# BufferBiasAmp.net
KiCad netlist of a schematic drawn in Altium Designer
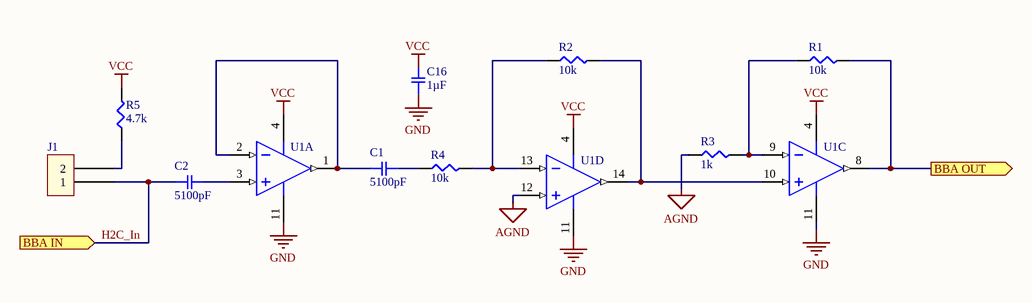
[diagram p0: BufferBiasAmp.SchDoc]

(export (version "E")
  (design (tool "Eeschema 10.0.6"))
  (components
    (comp (ref "C1")
      (value "5100pF")
      (footprint "SMD-0603C")
      (description "CAP CER 5100PF 50V U2J 0603")
      (fields
        (field (name "MANUFACTURER") "Murata Electronics North America")
        (field (name "MANUFACTURER PART NUMBER") "GRM1887U1H512JA01D")
      )
      (libsource (lib "capacitor_murata_0603") (part "GRM1887U1H512JA01D"))
    )
    (comp (ref "C2")
      (value "5100pF")
      (footprint "SMD-0603C")
      (description "CAP CER 5100PF 50V U2J 0603")
      (fields
        (field (name "DIGI-KEY PART NUMBER") "490-6399-1-ND")
        (field (name "PART NUMBER") "GRM1887U1H512JA01D")
      )
      (libsource (lib "capacitor_murata_0603") (part "GRM1887U1H512JA01D"))
    )
    (comp (ref "C16")
      (value "1µF")
      (footprint "SMD-0603C")
      (description "CAP CER 1UF 16V X7R 0603")
      (fields
        (field (name "MANUFACTURER") "Samsung Electro-Mechanics")
        (field (name "MANUFACTURER PART NUMBER") "CL10A105KA8NNNC")
      )
      (libsource (lib "capacitor_murata_0603") (part "GCM188R71C105KA64D"))
    )
    (comp (ref "J1")
      (value "Header")
      (footprint "1x2 Header")
      (description "CONN HEADER VERT 2POS 2.54MM")
      (libsource (lib "URC_Lib") (part "1x2 Header"))
    )
    (comp (ref "R1")
      (value "10k")
      (footprint "SMD-0603-RES")
      (description "RES SMD 10K OHM 1% 1/10W 0603")
      (fields
        (field (name "MANUFACTURER") "Panasonic Electronic Components")
        (field (name "MANUFACTURER PART NUMBER") "RNCP0603FTD10K0")
      )
      (libsource (lib "Panasonic_resistor_0603") (part "ERJ-3EKF1002V"))
    )
    (comp (ref "R2")
      (value "10k")
      (footprint "SMD-0603-RES")
      (description "RES SMD 10K OHM 1% 1/10W 0603")
      (fields
        (field (name "MANUFACTURER") "Panasonic Electronic Components")
        (field (name "MANUFACTURER PART NUMBER") "RNCP0603FTD10K0")
      )
      (libsource (lib "Panasonic_resistor_0603") (part "ERJ-3EKF1002V"))
    )
    (comp (ref "R3")
      (value "1k")
      (footprint "SMD-0603-RES")
      (description "RES SMD 1K OHM 1% 1/10W 0603")
      (fields
        (field (name "MANUFACTURER") "Stackpole Electronics Inc")
        (field (name "MANUFACTURER PART NUMBER") "RNCP0603FTD1K00")
      )
      (libsource (lib "Panasonic_resistor_0603") (part "ERJ-3EKF1001V"))
    )
    (comp (ref "R4")
      (value "10k")
      (footprint "SMD-0603-RES")
      (description "RES SMD 10K OHM 1% 1/10W 0603")
      (fields
        (field (name "MANUFACTURER") "Panasonic Electronic Components")
        (field (name "MANUFACTURER PART NUMBER") "RNCP0603FTD10K0")
      )
      (libsource (lib "Panasonic_resistor_0603") (part "ERJ-3EKF1002V"))
    )
    (comp (ref "R5")
      (value "4.7k")
      (footprint "SMD-0603-RES")
      (description "RES SMD 4.7K OHM 1% 1/10W 0603")
      (fields
        (field (name "MANUFACTURER") "Panasonic Electronic Components")
        (field (name "MANUFACTURER PART NUMBER") "ERJ-3EKF4701V")
      )
      (libsource (lib "Panasonic_resistor_0603") (part "ERJ-3EKF4701V"))
    )
    (comp (ref "U1")
      (value "OPA1604AIPWR")
      (footprint "PW0014A_N")
      (fields (field (name "MANUFACTURER") "Texas Instruments"))
      (libsource (lib "Altium Content Vault") (part "TI-OPA16X4_4XXX-14"))
    )
  )
  (nets
    (net (code "1") (name "/BBA OUT") (class "Default")
      (node (ref "R1") (pin "2") (pinfunction "2_2") (pintype "passive"))
      (node (ref "U1") (pin "8") (pinfunction "OUT_C_8") (pintype "output"))
    )
    (net (code "2") (name "/H2C_In") (class "Default")
      (node (ref "C2") (pin "1") (pinfunction "1_1") (pintype "passive"))
      (node (ref "J1") (pin "1") (pinfunction "1_1") (pintype "passive"))
    )
    (net (code "3") (name "AGND") (class "Default")
      (node (ref "R3") (pin "1") (pinfunction "1_1") (pintype "passive"))
      (node (ref "U1") (pin "12") (pinfunction "IN_D+_12") (pintype "input"))
    )
    (net (code "4") (name "GND") (class "Default")
      (node (ref "C16") (pin "1") (pinfunction "1_1") (pintype "passive"))
      (node (ref "U1") (pin "11") (pinfunction "V-_11") (pintype "power_in"))
    )
    (net (code "5") (name "Net-(C1-Pad1)") (class "Default")
      (node (ref "C1") (pin "1") (pinfunction "1_1") (pintype "passive"))
      (node (ref "R4") (pin "1") (pinfunction "1_1") (pintype "passive"))
    )
    (net (code "6") (name "Net-(J1-Pad2)") (class "Default")
      (node (ref "J1") (pin "2") (pinfunction "2_2") (pintype "passive"))
      (node (ref "R5") (pin "1") (pinfunction "1_1") (pintype "passive"))
    )
    (net (code "7") (name "Net-(U1A-IN_A+)") (class "Default")
      (node (ref "C2") (pin "2") (pinfunction "2_2") (pintype "passive"))
      (node (ref "U1") (pin "3") (pinfunction "IN_A+_3") (pintype "input"))
    )
    (net (code "8") (name "Net-(U1A-IN_A-)") (class "Default")
      (node (ref "C1") (pin "2") (pinfunction "2_2") (pintype "passive"))
      (node (ref "U1") (pin "1") (pinfunction "OUT_A_1") (pintype "output"))
      (node (ref "U1") (pin "2") (pinfunction "IN_A-_2") (pintype "input"))
    )
    (net (code "9") (name "Net-(U1C-IN_C+)") (class "Default")
      (node (ref "R2") (pin "2") (pinfunction "2_2") (pintype "passive"))
      (node (ref "U1") (pin "10") (pinfunction "IN_C+_10") (pintype "input"))
      (node (ref "U1") (pin "14") (pinfunction "OUT_D_14") (pintype "output"))
    )
    (net (code "10") (name "Net-(U1C-IN_C-)") (class "Default")
      (node (ref "R1") (pin "1") (pinfunction "1_1") (pintype "passive"))
      (node (ref "R3") (pin "2") (pinfunction "2_2") (pintype "passive"))
      (node (ref "U1") (pin "9") (pinfunction "IN_C-_9") (pintype "input"))
    )
    (net (code "11") (name "Net-(U1D-IN_D-)") (class "Default")
      (node (ref "R2") (pin "1") (pinfunction "1_1") (pintype "passive"))
      (node (ref "R4") (pin "2") (pinfunction "2_2") (pintype "passive"))
      (node (ref "U1") (pin "13") (pinfunction "IN_D-_13") (pintype "input"))
    )
    (net (code "12") (name "VCC") (class "Default")
      (node (ref "C16") (pin "2") (pinfunction "2_2") (pintype "passive"))
      (node (ref "R5") (pin "2") (pinfunction "2_2") (pintype "passive"))
      (node (ref "U1") (pin "4") (pinfunction "V+_4") (pintype "power_in"))
    )
  )
)
